# Fi-Pi.net
KiCad netlist of a schematic drawn in EAGLE
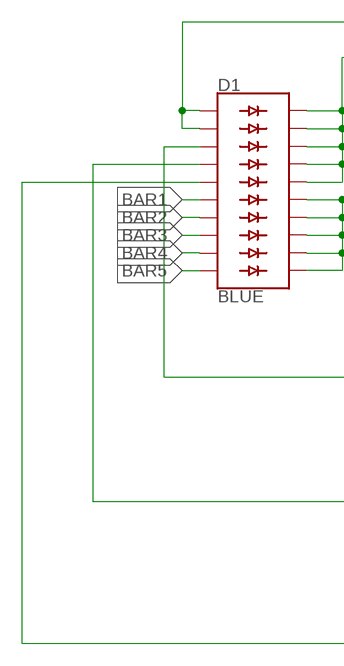
[diagram p0: schematic, sheet 1, part 1 of 2]
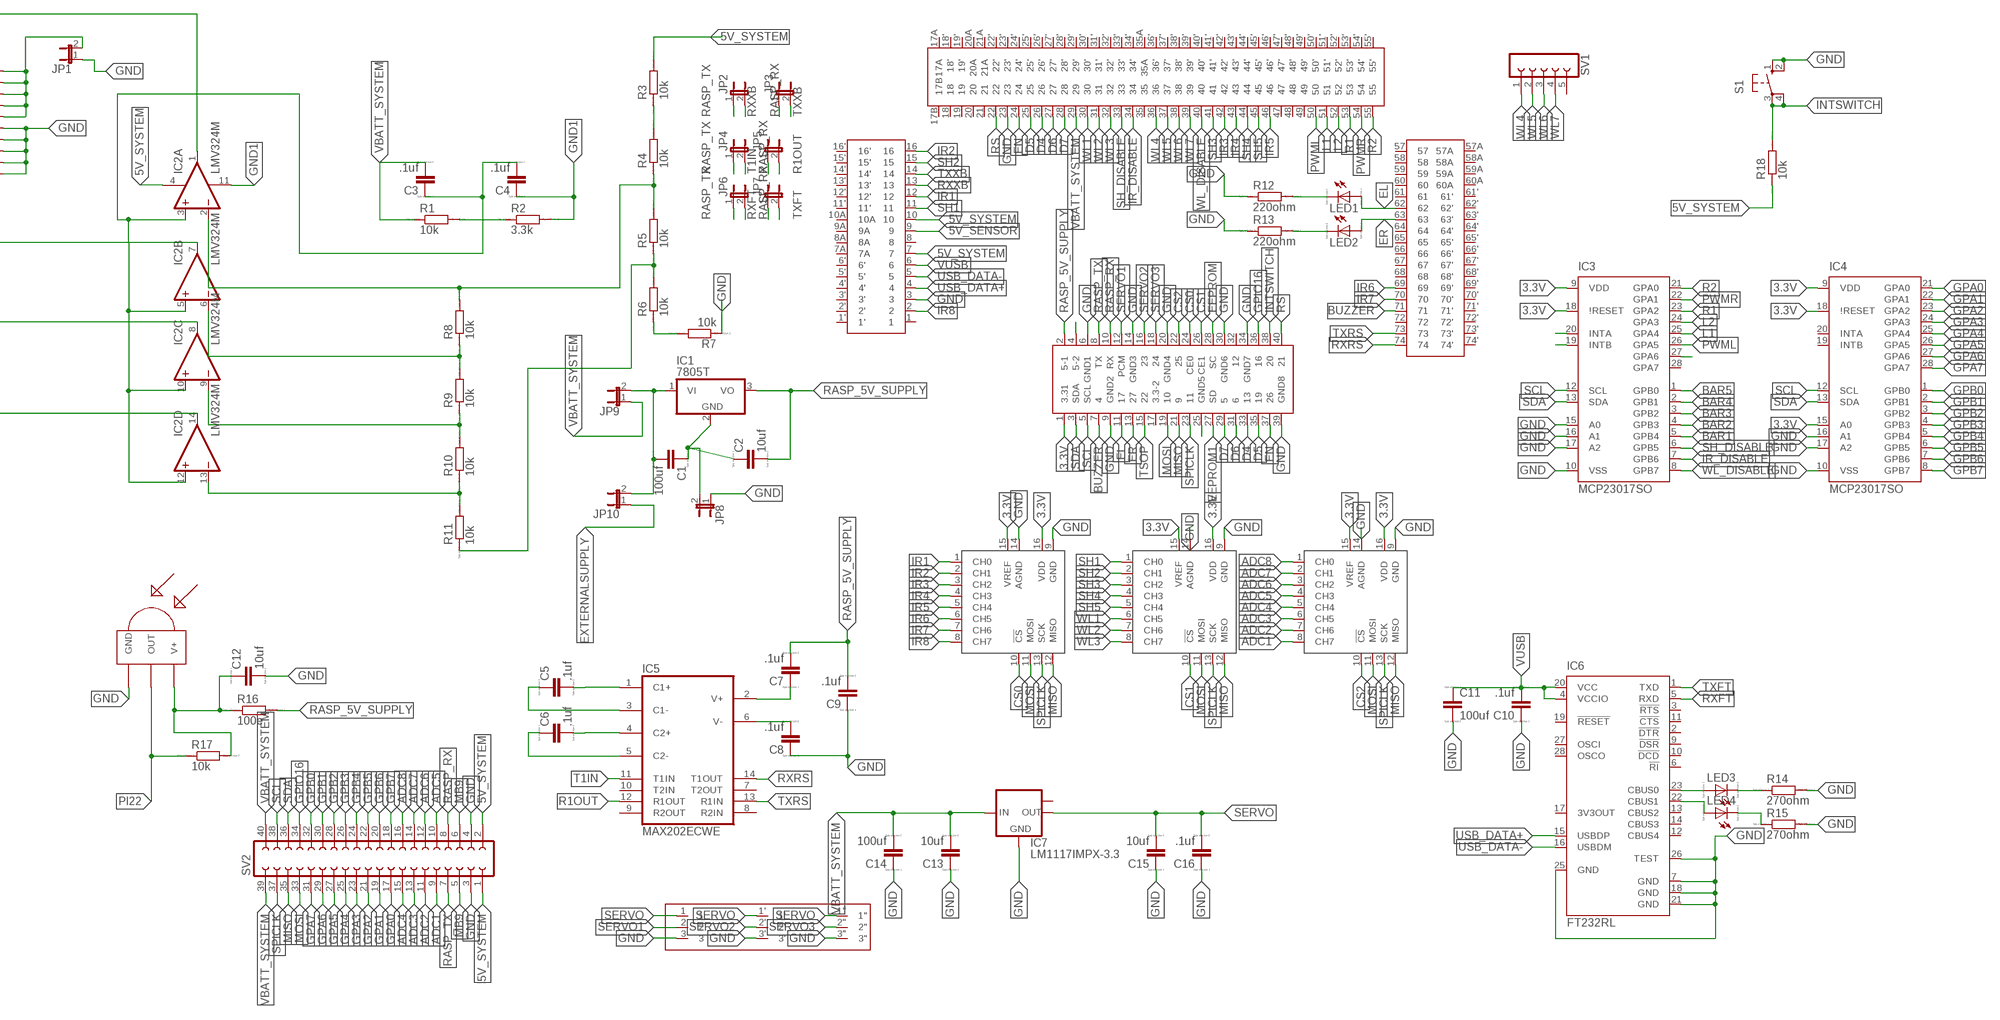
[diagram p1: schematic, sheet 1, part 2 of 2]

(export (version "E")
  (design (tool "Eeschema 10.0.6"))
  (components
    (comp (ref "C1")
      (value "100uf")
      (footprint "eagle-import:C1206")
      (libsource (lib "eagle-import") (part "CC1206"))
    )
    (comp (ref "C2")
      (value "10uf")
      (footprint "eagle-import:C1206")
      (libsource (lib "eagle-import") (part "CC1206"))
    )
    (comp (ref "C3")
      (value ".1uf")
      (footprint "eagle-import:C1206")
      (libsource (lib "eagle-import") (part "CC1206"))
    )
    (comp (ref "C4")
      (value ".1uf")
      (footprint "eagle-import:C1206")
      (libsource (lib "eagle-import") (part "CC1206"))
    )
    (comp (ref "C5")
      (value ".1uf")
      (footprint "eagle-import:C1206")
      (libsource (lib "eagle-import") (part "CC1206"))
    )
    (comp (ref "C6")
      (value ".1uf")
      (footprint "eagle-import:C1206")
      (libsource (lib "eagle-import") (part "CC1206"))
    )
    (comp (ref "C7")
      (value ".1uf")
      (footprint "eagle-import:C1206")
      (libsource (lib "eagle-import") (part "CC1206"))
    )
    (comp (ref "C8")
      (value ".1uf")
      (footprint "eagle-import:C1206")
      (libsource (lib "eagle-import") (part "CC1206"))
    )
    (comp (ref "C9")
      (value ".1uf")
      (footprint "eagle-import:C1206")
      (libsource (lib "eagle-import") (part "CC1206"))
    )
    (comp (ref "C10")
      (value ".1uf")
      (footprint "eagle-import:C1206")
      (libsource (lib "eagle-import") (part "CC1206"))
    )
    (comp (ref "C11")
      (value "100uf")
      (footprint "eagle-import:C1206")
      (libsource (lib "eagle-import") (part "CC1206"))
    )
    (comp (ref "C12")
      (value "10uf")
      (footprint "eagle-import:C1206")
      (libsource (lib "eagle-import") (part "CC1206"))
    )
    (comp (ref "C13")
      (value "10uf")
      (footprint "eagle-import:C1206")
      (libsource (lib "eagle-import") (part "CC1206"))
    )
    (comp (ref "C14")
      (value "100uf")
      (footprint "eagle-import:C1206")
      (libsource (lib "eagle-import") (part "CC1206"))
    )
    (comp (ref "C15")
      (value "10uf")
      (footprint "eagle-import:C1206")
      (libsource (lib "eagle-import") (part "CC1206"))
    )
    (comp (ref "C16")
      (value ".1uf")
      (footprint "eagle-import:C1206")
      (libsource (lib "eagle-import") (part "CC1206"))
    )
    (comp (ref "D1")
      (value "BLUE")
      (footprint "eagle-import:LED_BARGRAPH_10")
      (libsource (lib "eagle-import") (part "LED_BARGRAPH_10BLUE"))
    )
    (comp (ref "IC1")
      (value "7805T")
      (footprint "eagle-import:TO220H")
      (libsource (lib "eagle-import") (part "78T05"))
    )
    (comp (ref "IC2")
      (value "LMV324M")
      (footprint "eagle-import:SO14")
      (libsource (lib "eagle-import") (part "LMV324?M"))
    )
    (comp (ref "IC3")
      (value "MCP23017SO")
      (footprint "eagle-import:SO28W")
      (libsource (lib "eagle-import") (part "MCP23017SO"))
    )
    (comp (ref "IC4")
      (value "MCP23017SO")
      (footprint "eagle-import:SO28W")
      (libsource (lib "eagle-import") (part "MCP23017SO"))
    )
    (comp (ref "IC5")
      (value "MAX202ECWE")
      (footprint "eagle-import:SO16L")
      (fields (field (name "MPN") "MAX202ECWE+T"))
      (libsource (lib "eagle-import") (part "MAX202ECWE"))
    )
    (comp (ref "IC6")
      (value "FT232RL")
      (footprint "eagle-import:SSOP28")
      (libsource (lib "eagle-import") (part "FT232RL"))
    )
    (comp (ref "IC7")
      (value "LM1117IMPX-3.3")
      (footprint "eagle-import:SOT223")
      (libsource (lib "eagle-import") (part "LM1117IMPX-3.3"))
    )
    (comp (ref "JP1")
      (value "JP1E")
      (footprint "eagle-import:JP1")
      (libsource (lib "eagle-import") (part "JP1E"))
    )
    (comp (ref "JP2")
      (value "JP1E")
      (footprint "eagle-import:JP1")
      (libsource (lib "eagle-import") (part "JP1E"))
    )
    (comp (ref "JP3")
      (value "JP1E")
      (footprint "eagle-import:JP1")
      (libsource (lib "eagle-import") (part "JP1E"))
    )
    (comp (ref "JP4")
      (value "JP1E")
      (footprint "eagle-import:JP1")
      (libsource (lib "eagle-import") (part "JP1E"))
    )
    (comp (ref "JP5")
      (value "JP1E")
      (footprint "eagle-import:JP1")
      (libsource (lib "eagle-import") (part "JP1E"))
    )
    (comp (ref "JP6")
      (value "JP1E")
      (footprint "eagle-import:JP1")
      (libsource (lib "eagle-import") (part "JP1E"))
    )
    (comp (ref "JP7")
      (value "JP1E")
      (footprint "eagle-import:JP1")
      (libsource (lib "eagle-import") (part "JP1E"))
    )
    (comp (ref "JP8")
      (value "JP1E")
      (footprint "eagle-import:JP1")
      (libsource (lib "eagle-import") (part "JP1E"))
    )
    (comp (ref "JP9")
      (value "JP1E")
      (footprint "eagle-import:JP1")
      (libsource (lib "eagle-import") (part "JP1E"))
    )
    (comp (ref "JP10")
      (value "JP1E")
      (footprint "eagle-import:JP1")
      (libsource (lib "eagle-import") (part "JP1E"))
    )
    (comp (ref "LED1")
      (value "LED_E")
      (footprint "eagle-import:LED_1206")
      (libsource (lib "eagle-import") (part "LED_E"))
    )
    (comp (ref "LED2")
      (value "LED_E")
      (footprint "eagle-import:LED_1206")
      (libsource (lib "eagle-import") (part "LED_E"))
    )
    (comp (ref "LED3")
      (value "LED_E")
      (footprint "eagle-import:LED_1206")
      (libsource (lib "eagle-import") (part "LED_E"))
    )
    (comp (ref "LED4")
      (value "LED_E")
      (footprint "eagle-import:LED_1206")
      (libsource (lib "eagle-import") (part "LED_E"))
    )
    (comp (ref "R1")
      (value "10k")
      (footprint "eagle-import:R1206")
      (libsource (lib "eagle-import") (part "RR1206"))
    )
    (comp (ref "R2")
      (value "3.3k")
      (footprint "eagle-import:R1206")
      (libsource (lib "eagle-import") (part "RR1206"))
    )
    (comp (ref "R3")
      (value "10k")
      (footprint "eagle-import:R1206")
      (libsource (lib "eagle-import") (part "RR1206"))
    )
    (comp (ref "R4")
      (value "10k")
      (footprint "eagle-import:R1206")
      (libsource (lib "eagle-import") (part "RR1206"))
    )
    (comp (ref "R5")
      (value "10k")
      (footprint "eagle-import:R1206")
      (libsource (lib "eagle-import") (part "RR1206"))
    )
    (comp (ref "R6")
      (value "10k")
      (footprint "eagle-import:R1206")
      (libsource (lib "eagle-import") (part "RR1206"))
    )
    (comp (ref "R7")
      (value "10k")
      (footprint "eagle-import:R1206")
      (libsource (lib "eagle-import") (part "RR1206"))
    )
    (comp (ref "R8")
      (value "10k")
      (footprint "eagle-import:R1206")
      (libsource (lib "eagle-import") (part "RR1206"))
    )
    (comp (ref "R9")
      (value "10k")
      (footprint "eagle-import:R1206")
      (libsource (lib "eagle-import") (part "RR1206"))
    )
    (comp (ref "R10")
      (value "10k")
      (footprint "eagle-import:R1206")
      (libsource (lib "eagle-import") (part "RR1206"))
    )
    (comp (ref "R11")
      (value "10k")
      (footprint "eagle-import:R1206")
      (libsource (lib "eagle-import") (part "RR1206"))
    )
    (comp (ref "R12")
      (value "220ohm")
      (footprint "eagle-import:R1206")
      (libsource (lib "eagle-import") (part "RR1206"))
    )
    (comp (ref "R13")
      (value "220ohm")
      (footprint "eagle-import:R1206")
      (libsource (lib "eagle-import") (part "RR1206"))
    )
    (comp (ref "R14")
      (value "270ohm")
      (footprint "eagle-import:R1206")
      (libsource (lib "eagle-import") (part "RR1206"))
    )
    (comp (ref "R15")
      (value "270ohm")
      (footprint "eagle-import:R1206")
      (libsource (lib "eagle-import") (part "RR1206"))
    )
    (comp (ref "R16")
      (value "100e")
      (footprint "eagle-import:R1206")
      (libsource (lib "eagle-import") (part "RR1206"))
    )
    (comp (ref "R17")
      (value "10k")
      (footprint "eagle-import:R1206")
      (libsource (lib "eagle-import") (part "RR1206"))
    )
    (comp (ref "R18")
      (value "10k")
      (footprint "eagle-import:R1206")
      (libsource (lib "eagle-import") (part "RR1206"))
    )
    (comp (ref "S1")
      (value "10-XX")
      (footprint "eagle-import:B3F-10XX")
      (fields (field (name "MPN") "B3F-1000"))
      (libsource (lib "eagle-import") (part "10-XX"))
    )
    (comp (ref "SV1")
      (value "FE05-1")
      (footprint "eagle-import:FE05-1")
      (libsource (lib "eagle-import") (part "FE05-1"))
    )
    (comp (ref "SV2")
      (value "FE20-2")
      (footprint "eagle-import:FE20-2")
      (libsource (lib "eagle-import") (part "FE20-2"))
    )
    (comp (ref "U$1")
      (value "DAUGHTERBOARDDAUGHTERBOARD")
      (footprint "eagle-import:DAUGHTERBOARD")
      (libsource (lib "eagle-import") (part "DAUGHTERBOARDDAUGHTERBOARD"))
    )
    (comp (ref "U$2")
      (value "MALE_HEADER")
      (footprint "eagle-import:MALE_HEADER_PACKAGE")
      (libsource (lib "eagle-import") (part "MALE_HEADER"))
    )
    (comp (ref "U$3")
      (value "MCP3008SL")
      (footprint "eagle-import:SO16")
      (libsource (lib "eagle-import") (part "MCP3008SL"))
    )
    (comp (ref "U$4")
      (value "MCP3008SL")
      (footprint "eagle-import:SO16")
      (libsource (lib "eagle-import") (part "MCP3008SL"))
    )
    (comp (ref "U$5")
      (value "MCP3008SL")
      (footprint "eagle-import:SO16")
      (libsource (lib "eagle-import") (part "MCP3008SL"))
    )
    (comp (ref "U$6")
      (value "TSOP1738")
      (footprint "eagle-import:TSOP17XX")
      (libsource (lib "eagle-import") (part "TSOP1738"))
    )
    (comp (ref "U$7")
      (value "SERVO")
      (footprint "eagle-import:SERVO")
      (libsource (lib "eagle-import") (part "SERVO"))
    )
  )
  (nets
    (net (code "1") (name "3.3V") (class "Default")
      (node (ref "IC3") (pin "18") (pinfunction "\\~{RESET}_18") (pintype "input"))
      (node (ref "IC3") (pin "9") (pinfunction "VDD_9") (pintype "power_in"))
      (node (ref "IC4") (pin "15") (pinfunction "A0_15") (pintype "input"))
      (node (ref "IC4") (pin "18") (pinfunction "\\~{RESET}_18") (pintype "input"))
      (node (ref "IC4") (pin "9") (pinfunction "VDD_9") (pintype "power_in"))
      (node (ref "U$2") (pin "1") (pinfunction "3.31_1") (pintype "bidirectional"))
      (node (ref "U$3") (pin "15") (pinfunction "VREF_15") (pintype "power_in"))
      (node (ref "U$3") (pin "16") (pinfunction "VDD_16") (pintype "power_in"))
      (node (ref "U$4") (pin "15") (pinfunction "VREF_15") (pintype "power_in"))
      (node (ref "U$4") (pin "16") (pinfunction "VDD_16") (pintype "power_in"))
      (node (ref "U$5") (pin "15") (pinfunction "VREF_15") (pintype "power_in"))
      (node (ref "U$5") (pin "16") (pinfunction "VDD_16") (pintype "power_in"))
    )
    (net (code "2") (name "5V_SENSOR") (class "Default")
      (node (ref "U$1") (pin "9") (pinfunction "9_9") (pintype "output"))
    )
    (net (code "3") (name "5V_SYSTEM") (class "Default")
      (node (ref "IC2") (pin "4") (pinfunction "V+_4") (pintype "power_in"))
      (node (ref "R18") (pin "1") (pinfunction "1_1") (pintype "passive"))
      (node (ref "R3") (pin "2") (pinfunction "2_2") (pintype "passive"))
      (node (ref "SV2") (pin "1") (pinfunction "1_1") (pintype "passive"))
      (node (ref "SV2") (pin "2") (pinfunction "2_2") (pintype "passive"))
      (node (ref "U$1") (pin "10") (pinfunction "10_10") (pintype "output"))
      (node (ref "U$1") (pin "7") (pinfunction "7_7") (pintype "output"))
    )
    (net (code "4") (name "ADC1") (class "Default")
      (node (ref "SV2") (pin "9") (pinfunction "9_9") (pintype "passive"))
      (node (ref "U$5") (pin "8") (pinfunction "CH7_8") (pintype "input"))
    )
    (net (code "5") (name "ADC2") (class "Default")
      (node (ref "SV2") (pin "11") (pinfunction "11_11") (pintype "passive"))
      (node (ref "U$5") (pin "7") (pinfunction "CH6_7") (pintype "input"))
    )
    (net (code "6") (name "ADC3") (class "Default")
      (node (ref "SV2") (pin "13") (pinfunction "13_13") (pintype "passive"))
      (node (ref "U$5") (pin "6") (pinfunction "CH5_6") (pintype "input"))
    )
    (net (code "7") (name "ADC4") (class "Default")
      (node (ref "SV2") (pin "15") (pinfunction "15_15") (pintype "passive"))
      (node (ref "U$5") (pin "5") (pinfunction "CH4_5") (pintype "input"))
    )
    (net (code "8") (name "ADC5") (class "Default")
      (node (ref "SV2") (pin "10") (pinfunction "10_10") (pintype "passive"))
      (node (ref "U$5") (pin "4") (pinfunction "CH3_4") (pintype "input"))
    )
    (net (code "9") (name "ADC6") (class "Default")
      (node (ref "SV2") (pin "12") (pinfunction "12_12") (pintype "passive"))
      (node (ref "U$5") (pin "3") (pinfunction "CH2_3") (pintype "input"))
    )
    (net (code "10") (name "ADC7") (class "Default")
      (node (ref "SV2") (pin "14") (pinfunction "14_14") (pintype "passive"))
      (node (ref "U$5") (pin "2") (pinfunction "CH1_2") (pintype "input"))
    )
    (net (code "11") (name "ADC8") (class "Default")
      (node (ref "SV2") (pin "16") (pinfunction "16_16") (pintype "passive"))
      (node (ref "U$5") (pin "1") (pinfunction "CH0_1") (pintype "input"))
    )
    (net (code "12") (name "BAR1") (class "Default")
      (node (ref "D1") (pin "6") (pinfunction "A5_6") (pintype "passive"))
      (node (ref "IC3") (pin "5") (pinfunction "GPB4_5") (pintype "bidirectional"))
    )
    (net (code "13") (name "BAR2") (class "Default")
      (node (ref "D1") (pin "7") (pinfunction "A6_7") (pintype "passive"))
      (node (ref "IC3") (pin "4") (pinfunction "GPB3_4") (pintype "bidirectional"))
    )
    (net (code "14") (name "BAR3") (class "Default")
      (node (ref "D1") (pin "8") (pinfunction "A7_8") (pintype "passive"))
      (node (ref "IC3") (pin "3") (pinfunction "GPB2_3") (pintype "bidirectional"))
    )
    (net (code "15") (name "BAR4") (class "Default")
      (node (ref "D1") (pin "9") (pinfunction "A8_9") (pintype "passive"))
      (node (ref "IC3") (pin "2") (pinfunction "GPB1_2") (pintype "bidirectional"))
    )
    (net (code "16") (name "BAR5") (class "Default")
      (node (ref "D1") (pin "10") (pinfunction "A9_10") (pintype "passive"))
      (node (ref "IC3") (pin "1") (pinfunction "GPB0_1") (pintype "bidirectional"))
    )
    (net (code "17") (name "BUZZER") (class "Default")
      (node (ref "U$1") (pin "71") (pinfunction "71_71") (pintype "output"))
      (node (ref "U$2") (pin "7") (pinfunction "4_7") (pintype "bidirectional"))
    )
    (net (code "18") (name "CS0") (class "Default")
      (node (ref "U$2") (pin "24") (pinfunction "CE0_24") (pintype "bidirectional"))
      (node (ref "U$3") (pin "10") (pinfunction "~{CS}_10") (pintype "input"))
    )
    (net (code "19") (name "CS1") (class "Default")
      (node (ref "U$2") (pin "26") (pinfunction "CE1_26") (pintype "bidirectional"))
      (node (ref "U$4") (pin "10") (pinfunction "~{CS}_10") (pintype "input"))
    )
    (net (code "20") (name "CS2") (class "Default")
      (node (ref "U$2") (pin "22") (pinfunction "25_22") (pintype "bidirectional"))
      (node (ref "U$5") (pin "10") (pinfunction "~{CS}_10") (pintype "input"))
    )
    (net (code "21") (name "D4") (class "Default")
      (node (ref "U$1") (pin "26") (pinfunction "26_26") (pintype "output"))
      (node (ref "U$2") (pin "33") (pinfunction "13_33") (pintype "bidirectional"))
    )
    (net (code "22") (name "D5") (class "Default")
      (node (ref "U$1") (pin "25") (pinfunction "25_25") (pintype "output"))
      (node (ref "U$2") (pin "35") (pinfunction "19_35") (pintype "bidirectional"))
    )
    (net (code "23") (name "D6") (class "Default")
      (node (ref "U$1") (pin "27") (pinfunction "27_27") (pintype "output"))
      (node (ref "U$2") (pin "31") (pinfunction "6_31") (pintype "bidirectional"))
    )
    (net (code "24") (name "D7") (class "Default")
      (node (ref "U$1") (pin "28") (pinfunction "28_28") (pintype "output"))
      (node (ref "U$2") (pin "29") (pinfunction "5_29") (pintype "bidirectional"))
    )
    (net (code "25") (name "EEPROM") (class "Default")
      (node (ref "U$2") (pin "28") (pinfunction "SC_28") (pintype "bidirectional"))
    )
    (net (code "26") (name "EEPROM1") (class "Default")
      (node (ref "U$2") (pin "27") (pinfunction "SD_27") (pintype "bidirectional"))
    )
    (net (code "27") (name "EL") (class "Default")
      (node (ref "LED1") (pin "A") (pinfunction "A_A") (pintype "passive"))
      (node (ref "U$1") (pin "62") (pinfunction "62_62") (pintype "output"))
      (node (ref "U$2") (pin "11") (pinfunction "17_11") (pintype "bidirectional"))
    )
    (net (code "28") (name "EN") (class "Default")
      (node (ref "U$1") (pin "24") (pinfunction "24_24") (pintype "output"))
      (node (ref "U$2") (pin "37") (pinfunction "26_37") (pintype "bidirectional"))
    )
    (net (code "29") (name "ER") (class "Default")
      (node (ref "LED2") (pin "A") (pinfunction "A_A") (pintype "passive"))
      (node (ref "U$1") (pin "63") (pinfunction "63_63") (pintype "output"))
      (node (ref "U$2") (pin "13") (pinfunction "27_13") (pintype "bidirectional"))
    )
    (net (code "30") (name "EXTERNALSUPPLY") (class "Default")
      (node (ref "JP10") (pin "1") (pinfunction "1_1") (pintype "passive"))
    )
    (net (code "31") (name "GND") (class "Default")
      (node (ref "C10") (pin "1") (pinfunction "1_1") (pintype "passive"))
      (node (ref "C11") (pin "2") (pinfunction "2_2") (pintype "passive"))
      (node (ref "C12") (pin "2") (pinfunction "2_2") (pintype "passive"))
      (node (ref "C13") (pin "1") (pinfunction "1_1") (pintype "passive"))
      (node (ref "C14") (pin "1") (pinfunction "1_1") (pintype "passive"))
      (node (ref "C15") (pin "1") (pinfunction "1_1") (pintype "passive"))
      (node (ref "C16") (pin "1") (pinfunction "1_1") (pintype "passive"))
      (node (ref "C8") (pin "1") (pinfunction "1_1") (pintype "passive"))
      (node (ref "C9") (pin "1") (pinfunction "1_1") (pintype "passive"))
      (node (ref "D1") (pin "11") (pinfunction "C9_11") (pintype "passive"))
      (node (ref "D1") (pin "12") (pinfunction "C8_12") (pintype "passive"))
      (node (ref "D1") (pin "13") (pinfunction "C7_13") (pintype "passive"))
      (node (ref "D1") (pin "14") (pinfunction "C6_14") (pintype "passive"))
      (node (ref "D1") (pin "15") (pinfunction "C5_15") (pintype "passive"))
      (node (ref "IC3") (pin "10") (pinfunction "VSS_10") (pintype "power_in"))
      (node (ref "IC3") (pin "15") (pinfunction "A0_15") (pintype "input"))
      (node (ref "IC3") (pin "16") (pinfunction "A1_16") (pintype "input"))
      (node (ref "IC3") (pin "17") (pinfunction "A2_17") (pintype "input"))
      (node (ref "IC4") (pin "10") (pinfunction "VSS_10") (pintype "power_in"))
      (node (ref "IC4") (pin "16") (pinfunction "A1_16") (pintype "input"))
      (node (ref "IC4") (pin "17") (pinfunction "A2_17") (pintype "input"))
      (node (ref "IC6") (pin "18") (pinfunction "GND_18") (pintype "power_in"))
      (node (ref "IC6") (pin "21") (pinfunction "GND_21") (pintype "power_in"))
      (node (ref "IC6") (pin "25") (pinfunction "GND_25") (pintype "power_in"))
      (node (ref "IC6") (pin "26") (pinfunction "TEST_26") (pintype "input"))
      (node (ref "IC6") (pin "7") (pinfunction "GND_7") (pintype "power_in"))
      (node (ref "IC7") (pin "1") (pinfunction "GND_1") (pintype "input"))
      (node (ref "JP1") (pin "1") (pinfunction "1_1") (pintype "passive"))
      (node (ref "JP8") (pin "1") (pinfunction "1_1") (pintype "passive"))
      (node (ref "R12") (pin "1") (pinfunction "1_1") (pintype "passive"))
      (node (ref "R13") (pin "1") (pinfunction "1_1") (pintype "passive"))
      (node (ref "R14") (pin "2") (pinfunction "2_2") (pintype "passive"))
      (node (ref "R15") (pin "2") (pinfunction "2_2") (pintype "passive"))
      (node (ref "R7") (pin "1") (pinfunction "1_1") (pintype "passive"))
      (node (ref "S1") (pin "1") (pinfunction "S_1") (pintype "passive"))
      (node (ref "S1") (pin "2") (pinfunction "S1_2") (pintype "passive"))
      (node (ref "SV2") (pin "3") (pinfunction "3_3") (pintype "passive"))
      (node (ref "SV2") (pin "4") (pinfunction "4_4") (pintype "passive"))
      (node (ref "U$1") (pin "23") (pinfunction "23_23") (pintype "output"))
      (node (ref "U$1") (pin "3") (pinfunction "3_3") (pintype "output"))
      (node (ref "U$2") (pin "14") (pinfunction "GND3_14") (pintype "bidirectional"))
      (node (ref "U$2") (pin "20") (pinfunction "GND4_20") (pintype "bidirectional"))
      (node (ref "U$2") (pin "25") (pinfunction "GND5_25") (pintype "bidirectional"))
      (node (ref "U$2") (pin "30") (pinfunction "GND6_30") (pintype "bidirectional"))
      (node (ref "U$2") (pin "34") (pinfunction "GND7_34") (pintype "bidirectional"))
      (node (ref "U$2") (pin "39") (pinfunction "GND8_39") (pintype "bidirectional"))
      (node (ref "U$2") (pin "6") (pinfunction "GND1_6") (pintype "bidirectional"))
      (node (ref "U$2") (pin "9") (pinfunction "GND2_9") (pintype "bidirectional"))
      (node (ref "U$3") (pin "14") (pinfunction "AGND_14") (pintype "power_in"))
      (node (ref "U$3") (pin "9") (pinfunction "GND_9") (pintype "power_in"))
      (node (ref "U$4") (pin "14") (pinfunction "AGND_14") (pintype "power_in"))
      (node (ref "U$4") (pin "9") (pinfunction "GND_9") (pintype "power_in"))
      (node (ref "U$5") (pin "14") (pinfunction "AGND_14") (pintype "power_in"))
      (node (ref "U$5") (pin "9") (pinfunction "GND_9") (pintype "power_in"))
      (node (ref "U$6") (pin "GND") (pinfunction "GND_GND") (pintype "bidirectional"))
      (node (ref "U$7") (pin "3") (pinfunction "3_3") (pintype "bidirectional"))
      (node (ref "U$7") (pin "3\"") (pinfunction "3\"_3\"") (pintype "bidirectional"))
      (node (ref "U$7") (pin "3'") (pinfunction "3'_3'") (pintype "bidirectional"))
    )
    (net (code "32") (name "GND1") (class "Default")
      (node (ref "C4") (pin "1") (pinfunction "1_1") (pintype "passive"))
      (node (ref "IC2") (pin "11") (pinfunction "V-_11") (pintype "power_in"))
      (node (ref "R2") (pin "2") (pinfunction "2_2") (pintype "passive"))
    )
    (net (code "33") (name "GPA0") (class "Default")
      (node (ref "IC4") (pin "21") (pinfunction "GPA0_21") (pintype "bidirectional"))
      (node (ref "SV2") (pin "17") (pinfunction "17_17") (pintype "passive"))
    )
    (net (code "34") (name "GPA1") (class "Default")
      (node (ref "IC4") (pin "22") (pinfunction "GPA1_22") (pintype "bidirectional"))
      (node (ref "SV2") (pin "19") (pinfunction "19_19") (pintype "passive"))
    )
    (net (code "35") (name "GPA2") (class "Default")
      (node (ref "IC4") (pin "23") (pinfunction "GPA2_23") (pintype "bidirectional"))
      (node (ref "SV2") (pin "21") (pinfunction "21_21") (pintype "passive"))
    )
    (net (code "36") (name "GPA3") (class "Default")
      (node (ref "IC4") (pin "24") (pinfunction "GPA3_24") (pintype "bidirectional"))
      (node (ref "SV2") (pin "23") (pinfunction "23_23") (pintype "passive"))
    )
    (net (code "37") (name "GPA4") (class "Default")
      (node (ref "IC4") (pin "25") (pinfunction "GPA4_25") (pintype "bidirectional"))
      (node (ref "SV2") (pin "25") (pinfunction "25_25") (pintype "passive"))
    )
    (net (code "38") (name "GPA5") (class "Default")
      (node (ref "IC4") (pin "26") (pinfunction "GPA5_26") (pintype "bidirectional"))
      (node (ref "SV2") (pin "27") (pinfunction "27_27") (pintype "passive"))
    )
    (net (code "39") (name "GPA6") (class "Default")
      (node (ref "IC4") (pin "27") (pinfunction "GPA6_27") (pintype "bidirectional"))
      (node (ref "SV2") (pin "29") (pinfunction "29_29") (pintype "passive"))
    )
    (net (code "40") (name "GPA7") (class "Default")
      (node (ref "IC4") (pin "28") (pinfunction "GPA7_28") (pintype "bidirectional"))
      (node (ref "SV2") (pin "31") (pinfunction "31_31") (pintype "passive"))
    )
    (net (code "41") (name "GPB0") (class "Default")
      (node (ref "IC4") (pin "1") (pinfunction "GPB0_1") (pintype "bidirectional"))
      (node (ref "SV2") (pin "32") (pinfunction "32_32") (pintype "passive"))
    )
    (net (code "42") (name "GPB1") (class "Default")
      (node (ref "IC4") (pin "2") (pinfunction "GPB1_2") (pintype "bidirectional"))
      (node (ref "SV2") (pin "30") (pinfunction "30_30") (pintype "passive"))
    )
    (net (code "43") (name "GPB2") (class "Default")
      (node (ref "IC4") (pin "3") (pinfunction "GPB2_3") (pintype "bidirectional"))
      (node (ref "SV2") (pin "28") (pinfunction "28_28") (pintype "passive"))
    )
    (net (code "44") (name "GPB3") (class "Default")
      (node (ref "IC4") (pin "4") (pinfunction "GPB3_4") (pintype "bidirectional"))
      (node (ref "SV2") (pin "26") (pinfunction "26_26") (pintype "passive"))
    )
    (net (code "45") (name "GPB4") (class "Default")
      (node (ref "IC4") (pin "5") (pinfunction "GPB4_5") (pintype "bidirectional"))
      (node (ref "SV2") (pin "24") (pinfunction "24_24") (pintype "passive"))
    )
    (net (code "46") (name "GPB5") (class "Default")
      (node (ref "IC4") (pin "6") (pinfunction "GPB5_6") (pintype "bidirectional"))
      (node (ref "SV2") (pin "22") (pinfunction "22_22") (pintype "passive"))
    )
    (net (code "47") (name "GPB6") (class "Default")
      (node (ref "IC4") (pin "7") (pinfunction "GPB6_7") (pintype "bidirectional"))
      (node (ref "SV2") (pin "20") (pinfunction "20_20") (pintype "passive"))
    )
    (net (code "48") (name "GPB7") (class "Default")
      (node (ref "IC4") (pin "8") (pinfunction "GPB7_8") (pintype "bidirectional"))
      (node (ref "SV2") (pin "18") (pinfunction "18_18") (pintype "passive"))
    )
    (net (code "49") (name "GPIO16") (class "Default")
      (node (ref "SV2") (pin "34") (pinfunction "34_34") (pintype "passive"))
      (node (ref "U$2") (pin "36") (pinfunction "16_36") (pintype "bidirectional"))
    )
    (net (code "50") (name "INTSWITCH") (class "Default")
      (node (ref "R18") (pin "2") (pinfunction "2_2") (pintype "passive"))
      (node (ref "S1") (pin "3") (pinfunction "P_3") (pintype "passive"))
      (node (ref "S1") (pin "4") (pinfunction "P1_4") (pintype "passive"))
      (node (ref "U$2") (pin "38") (pinfunction "20_38") (pintype "bidirectional"))
    )
    (net (code "51") (name "IR1") (class "Default")
      (node (ref "U$1") (pin "12") (pinfunction "12_12") (pintype "output"))
      (node (ref "U$3") (pin "1") (pinfunction "CH0_1") (pintype "input"))
    )
    (net (code "52") (name "IR2") (class "Default")
      (node (ref "U$1") (pin "16") (pinfunction "16_16") (pintype "output"))
      (node (ref "U$3") (pin "2") (pinfunction "CH1_2") (pintype "input"))
    )
    (net (code "53") (name "IR3") (class "Default")
      (node (ref "U$1") (pin "42") (pinfunction "42_42") (pintype "output"))
      (node (ref "U$3") (pin "3") (pinfunction "CH2_3") (pintype "input"))
    )
    (net (code "54") (name "IR4") (class "Default")
      (node (ref "U$1") (pin "43") (pinfunction "43_43") (pintype "output"))
      (node (ref "U$3") (pin "4") (pinfunction "CH3_4") (pintype "input"))
    )
    (net (code "55") (name "IR5") (class "Default")
      (node (ref "U$1") (pin "46") (pinfunction "46_46") (pintype "output"))
      (node (ref "U$3") (pin "5") (pinfunction "CH4_5") (pintype "input"))
    )
    (net (code "56") (name "IR6") (class "Default")
      (node (ref "U$1") (pin "69") (pinfunction "69_69") (pintype "output"))
      (node (ref "U$3") (pin "6") (pinfunction "CH5_6") (pintype "input"))
    )
    (net (code "57") (name "IR7") (class "Default")
      (node (ref "U$1") (pin "70") (pinfunction "70_70") (pintype "output"))
      (node (ref "U$3") (pin "7") (pinfunction "CH6_7") (pintype "input"))
    )
    (net (code "58") (name "IR8") (class "Default")
      (node (ref "U$1") (pin "2") (pinfunction "2_2") (pintype "output"))
      (node (ref "U$3") (pin "8") (pinfunction "CH7_8") (pintype "input"))
    )
    (net (code "59") (name "IR_DISABLE") (class "Default")
      (node (ref "IC3") (pin "7") (pinfunction "GPB6_7") (pintype "bidirectional"))
      (node (ref "U$1") (pin "34") (pinfunction "34_34") (pintype "output"))
    )
    (net (code "60") (name "L1") (class "Default")
      (node (ref "IC3") (pin "25") (pinfunction "GPA4_25") (pintype "bidirectional"))
      (node (ref "U$1") (pin "51") (pinfunction "51_51") (pintype "output"))
    )
    (net (code "61") (name "L2") (class "Default")
      (node (ref "IC3") (pin "24") (pinfunction "GPA3_24") (pintype "bidirectional"))
      (node (ref "U$1") (pin "52") (pinfunction "52_52") (pintype "output"))
    )
    (net (code "62") (name "MB9") (class "Default")
      (node (ref "SV2") (pin "5") (pinfunction "5_5") (pintype "passive"))
      (node (ref "SV2") (pin "6") (pinfunction "6_6") (pintype "passive"))
    )
    (net (code "63") (name "MISO") (class "Default")
      (node (ref "SV2") (pin "35") (pinfunction "35_35") (pintype "passive"))
      (node (ref "U$2") (pin "21") (pinfunction "9_21") (pintype "bidirectional"))
      (node (ref "U$3") (pin "12") (pinfunction "MISO_12") (pintype "output"))
      (node (ref "U$4") (pin "12") (pinfunction "MISO_12") (pintype "output"))
      (node (ref "U$5") (pin "12") (pinfunction "MISO_12") (pintype "output"))
    )
    (net (code "64") (name "MOSI") (class "Default")
      (node (ref "SV2") (pin "33") (pinfunction "33_33") (pintype "passive"))
      (node (ref "U$2") (pin "19") (pinfunction "10_19") (pintype "bidirectional"))
      (node (ref "U$3") (pin "11") (pinfunction "MOSI_11") (pintype "input"))
      (node (ref "U$4") (pin "11") (pinfunction "MOSI_11") (pintype "input"))
      (node (ref "U$5") (pin "11") (pinfunction "MOSI_11") (pintype "input"))
    )
    (net (code "65") (name "Net-(C12-Pad1)") (class "Default")
      (node (ref "C12") (pin "1") (pinfunction "1_1") (pintype "passive"))
      (node (ref "R16") (pin "1") (pinfunction "1_1") (pintype "passive"))
      (node (ref "R17") (pin "2") (pinfunction "2_2") (pintype "passive"))
      (node (ref "U$6") (pin "V+") (pinfunction "V+_V+") (pintype "bidirectional"))
    )
    (net (code "66") (name "Net-(D1-A)") (class "Default")
      (node (ref "D1") (pin "1") (pinfunction "A_1") (pintype "passive"))
      (node (ref "D1") (pin "2") (pinfunction "A1_2") (pintype "passive"))
      (node (ref "IC2") (pin "1") (pinfunction "OUT_1") (pintype "output"))
    )
    (net (code "67") (name "Net-(D1-A2)") (class "Default")
      (node (ref "D1") (pin "3") (pinfunction "A2_3") (pintype "passive"))
      (node (ref "IC2") (pin "7") (pinfunction "OUT_7") (pintype "output"))
    )
    (net (code "68") (name "Net-(D1-A3)") (class "Default")
      (node (ref "D1") (pin "4") (pinfunction "A3_4") (pintype "passive"))
      (node (ref "IC2") (pin "8") (pinfunction "OUT_8") (pintype "output"))
    )
    (net (code "69") (name "Net-(D1-A4)") (class "Default")
      (node (ref "D1") (pin "5") (pinfunction "A4_5") (pintype "passive"))
      (node (ref "IC2") (pin "14") (pinfunction "OUT_14") (pintype "output"))
    )
    (net (code "70") (name "Net-(D1-C)") (class "Default")
      (node (ref "D1") (pin "16") (pinfunction "C4_16") (pintype "passive"))
      (node (ref "D1") (pin "17") (pinfunction "C3_17") (pintype "passive"))
      (node (ref "D1") (pin "18") (pinfunction "C2_18") (pintype "passive"))
      (node (ref "D1") (pin "19") (pinfunction "C1_19") (pintype "passive"))
      (node (ref "D1") (pin "20") (pinfunction "C_20") (pintype "passive"))
      (node (ref "JP1") (pin "2") (pinfunction "2_2") (pintype "passive"))
    )
    (net (code "71") (name "Net-(IC1-GND)") (class "Default")
      (node (ref "C1") (pin "1") (pinfunction "1_1") (pintype "passive"))
      (node (ref "C2") (pin "1") (pinfunction "1_1") (pintype "passive"))
      (node (ref "IC1") (pin "2") (pinfunction "GND_2") (pintype "passive"))
      (node (ref "JP8") (pin "2") (pinfunction "2_2") (pintype "passive"))
    )
    (net (code "72") (name "Net-(IC2A-+IN)") (class "Default")
      (node (ref "C3") (pin "1") (pinfunction "1_1") (pintype "passive"))
      (node (ref "C4") (pin "2") (pinfunction "2_2") (pintype "passive"))
      (node (ref "IC2") (pin "10") (pinfunction "+IN_10") (pintype "input"))
      (node (ref "IC2") (pin "12") (pinfunction "+IN_12") (pintype "input"))
      (node (ref "IC2") (pin "3") (pinfunction "+IN_3") (pintype "input"))
      (node (ref "IC2") (pin "5") (pinfunction "+IN_5") (pintype "input"))
      (node (ref "R1") (pin "2") (pinfunction "2_2") (pintype "passive"))
      (node (ref "R2") (pin "1") (pinfunction "1_1") (pintype "passive"))
    )
    (net (code "73") (name "Net-(IC2A--IN)") (class "Default")
      (node (ref "IC2") (pin "2") (pinfunction "-IN_2") (pintype "input"))
      (node (ref "R4") (pin "1") (pinfunction "1_1") (pintype "passive"))
      (node (ref "R5") (pin "2") (pinfunction "2_2") (pintype "passive"))
      (node (ref "R8") (pin "2") (pinfunction "2_2") (pintype "passive"))
    )
    (net (code "74") (name "Net-(IC2B--IN)") (class "Default")
      (node (ref "IC2") (pin "6") (pinfunction "-IN_6") (pintype "input"))
      (node (ref "R8") (pin "1") (pinfunction "1_1") (pintype "passive"))
      (node (ref "R9") (pin "2") (pinfunction "2_2") (pintype "passive"))
    )
    (net (code "75") (name "Net-(IC2C--IN)") (class "Default")
      (node (ref "IC2") (pin "9") (pinfunction "-IN_9") (pintype "input"))
      (node (ref "R10") (pin "2") (pinfunction "2_2") (pintype "passive"))
      (node (ref "R9") (pin "1") (pinfunction "1_1") (pintype "passive"))
    )
    (net (code "76") (name "Net-(IC2D--IN)") (class "Default")
      (node (ref "IC2") (pin "13") (pinfunction "-IN_13") (pintype "input"))
      (node (ref "R10") (pin "1") (pinfunction "1_1") (pintype "passive"))
      (node (ref "R11") (pin "2") (pinfunction "2_2") (pintype "passive"))
    )
    (net (code "77") (name "Net-(IC5A-C1+)") (class "Default")
      (node (ref "C5") (pin "2") (pinfunction "2_2") (pintype "passive"))
      (node (ref "IC5") (pin "1") (pinfunction "C1+_1") (pintype "bidirectional"))
    )
    (net (code "78") (name "Net-(IC5A-C1-)") (class "Default")
      (node (ref "C5") (pin "1") (pinfunction "1_1") (pintype "passive"))
      (node (ref "IC5") (pin "3") (pinfunction "C1-_3") (pintype "bidirectional"))
    )
    (net (code "79") (name "Net-(IC5A-C2+)") (class "Default")
      (node (ref "C6") (pin "2") (pinfunction "2_2") (pintype "passive"))
      (node (ref "IC5") (pin "4") (pinfunction "C2+_4") (pintype "bidirectional"))
    )
    (net (code "80") (name "Net-(IC5A-C2-)") (class "Default")
      (node (ref "C6") (pin "1") (pinfunction "1_1") (pintype "passive"))
      (node (ref "IC5") (pin "5") (pinfunction "C2-_5") (pintype "bidirectional"))
    )
    (net (code "81") (name "Net-(IC5A-V+)") (class "Default")
      (node (ref "C7") (pin "1") (pinfunction "1_1") (pintype "passive"))
      (node (ref "IC5") (pin "2") (pinfunction "V+_2") (pintype "bidirectional"))
    )
    (net (code "82") (name "Net-(IC5A-V-)") (class "Default")
      (node (ref "C8") (pin "2") (pinfunction "2_2") (pintype "passive"))
      (node (ref "IC5") (pin "6") (pinfunction "V-_6") (pintype "bidirectional"))
    )
    (net (code "83") (name "Net-(IC6-CBUS0)") (class "Default")
      (node (ref "IC6") (pin "23") (pinfunction "CBUS0_23") (pintype "bidirectional"))
      (node (ref "LED3") (pin "A") (pinfunction "A_A") (pintype "passive"))
    )
    (net (code "84") (name "Net-(IC6-CBUS1)") (class "Default")
      (node (ref "IC6") (pin "22") (pinfunction "CBUS1_22") (pintype "bidirectional"))
      (node (ref "LED4") (pin "A") (pinfunction "A_A") (pintype "passive"))
    )
    (net (code "85") (name "Net-(LED1-PadC)") (class "Default")
      (node (ref "LED1") (pin "C") (pinfunction "C_C") (pintype "passive"))
      (node (ref "R12") (pin "2") (pinfunction "2_2") (pintype "passive"))
    )
    (net (code "86") (name "Net-(LED2-PadC)") (class "Default")
      (node (ref "LED2") (pin "C") (pinfunction "C_C") (pintype "passive"))
      (node (ref "R13") (pin "2") (pinfunction "2_2") (pintype "passive"))
    )
    (net (code "87") (name "Net-(LED3-PadC)") (class "Default")
      (node (ref "LED3") (pin "C") (pinfunction "C_C") (pintype "passive"))
      (node (ref "R14") (pin "1") (pinfunction "1_1") (pintype "passive"))
    )
    (net (code "88") (name "Net-(LED4-PadC)") (class "Default")
      (node (ref "LED4") (pin "C") (pinfunction "C_C") (pintype "passive"))
      (node (ref "R15") (pin "1") (pinfunction "1_1") (pintype "passive"))
    )
    (net (code "89") (name "Net-(R3-Pad1)") (class "Default")
      (node (ref "R3") (pin "1") (pinfunction "1_1") (pintype "passive"))
      (node (ref "R4") (pin "2") (pinfunction "2_2") (pintype "passive"))
    )
    (net (code "90") (name "Net-(R6-Pad1)") (class "Default")
      (node (ref "R6") (pin "1") (pinfunction "1_1") (pintype "passive"))
      (node (ref "R7") (pin "2") (pinfunction "2_2") (pintype "passive"))
    )
    (net (code "91") (name "Net-(R11-Pad1)") (class "Default")
      (node (ref "R11") (pin "1") (pinfunction "1_1") (pintype "passive"))
      (node (ref "R5") (pin "1") (pinfunction "1_1") (pintype "passive"))
      (node (ref "R6") (pin "2") (pinfunction "2_2") (pintype "passive"))
    )
    (net (code "92") (name "PI22") (class "Default")
      (node (ref "R17") (pin "1") (pinfunction "1_1") (pintype "passive"))
      (node (ref "U$6") (pin "OUT") (pinfunction "OUT_OUT") (pintype "bidirectional"))
    )
    (net (code "93") (name "PWML") (class "Default")
      (node (ref "IC3") (pin "26") (pinfunction "GPA5_26") (pintype "bidirectional"))
      (node (ref "U$1") (pin "50") (pinfunction "50_50") (pintype "output"))
    )
    (net (code "94") (name "PWMR") (class "Default")
      (node (ref "IC3") (pin "22") (pinfunction "GPA1_22") (pintype "bidirectional"))
      (node (ref "U$1") (pin "54") (pinfunction "54_54") (pintype "output"))
    )
    (net (code "95") (name "R1") (class "Default")
      (node (ref "IC3") (pin "23") (pinfunction "GPA2_23") (pintype "bidirectional"))
      (node (ref "U$1") (pin "53") (pinfunction "53_53") (pintype "output"))
    )
    (net (code "96") (name "R1OUT") (class "Default")
      (node (ref "IC5") (pin "12") (pinfunction "R1OUT_12") (pintype "output"))
      (node (ref "JP5") (pin "2") (pinfunction "2_2") (pintype "passive"))
    )
    (net (code "97") (name "R2") (class "Default")
      (node (ref "IC3") (pin "21") (pinfunction "GPA0_21") (pintype "bidirectional"))
      (node (ref "U$1") (pin "55") (pinfunction "55_55") (pintype "output"))
    )
    (net (code "98") (name "RASP_5V_SUPPLY") (class "Default")
      (node (ref "C2") (pin "2") (pinfunction "2_2") (pintype "passive"))
      (node (ref "C7") (pin "2") (pinfunction "2_2") (pintype "passive"))
      (node (ref "C9") (pin "2") (pinfunction "2_2") (pintype "passive"))
      (node (ref "IC1") (pin "3") (pinfunction "VO_3") (pintype "passive"))
      (node (ref "R16") (pin "2") (pinfunction "2_2") (pintype "passive"))
      (node (ref "U$2") (pin "2") (pinfunction "5-1_2") (pintype "bidirectional"))
    )
    (net (code "99") (name "RASP_RX") (class "Default")
      (node (ref "JP3") (pin "1") (pinfunction "1_1") (pintype "passive"))
      (node (ref "JP5") (pin "1") (pinfunction "1_1") (pintype "passive"))
      (node (ref "JP7") (pin "1") (pinfunction "1_1") (pintype "passive"))
      (node (ref "SV2") (pin "8") (pinfunction "8_8") (pintype "passive"))
      (node (ref "U$2") (pin "10") (pinfunction "RX_10") (pintype "bidirectional"))
    )
    (net (code "100") (name "RASP_TX") (class "Default")
      (node (ref "JP2") (pin "1") (pinfunction "1_1") (pintype "passive"))
      (node (ref "JP4") (pin "1") (pinfunction "1_1") (pintype "passive"))
      (node (ref "JP6") (pin "1") (pinfunction "1_1") (pintype "passive"))
      (node (ref "SV2") (pin "7") (pinfunction "7_7") (pintype "passive"))
      (node (ref "U$2") (pin "8") (pinfunction "TX_8") (pintype "bidirectional"))
    )
    (net (code "101") (name "RS") (class "Default")
      (node (ref "U$1") (pin "22") (pinfunction "22_22") (pintype "output"))
      (node (ref "U$2") (pin "40") (pinfunction "21_40") (pintype "bidirectional"))
    )
    (net (code "102") (name "RXFT") (class "Default")
      (node (ref "IC6") (pin "5") (pinfunction "RXD_5") (pintype "input"))
      (node (ref "JP6") (pin "2") (pinfunction "2_2") (pintype "passive"))
    )
    (net (code "103") (name "RXRS") (class "Default")
      (node (ref "IC5") (pin "14") (pinfunction "T1OUT_14") (pintype "output"))
      (node (ref "U$1") (pin "74") (pinfunction "74_74") (pintype "output"))
    )
    (net (code "104") (name "RXXB") (class "Default")
      (node (ref "JP2") (pin "2") (pinfunction "2_2") (pintype "passive"))
      (node (ref "U$1") (pin "13") (pinfunction "13_13") (pintype "output"))
    )
    (net (code "105") (name "SCL") (class "Default")
      (node (ref "IC3") (pin "12") (pinfunction "SCL_12") (pintype "input"))
      (node (ref "IC4") (pin "12") (pinfunction "SCL_12") (pintype "input"))
      (node (ref "SV2") (pin "38") (pinfunction "38_38") (pintype "passive"))
      (node (ref "U$2") (pin "5") (pinfunction "SCL_5") (pintype "bidirectional"))
    )
    (net (code "106") (name "SDA") (class "Default")
      (node (ref "IC3") (pin "13") (pinfunction "SDA_13") (pintype "bidirectional"))
      (node (ref "IC4") (pin "13") (pinfunction "SDA_13") (pintype "bidirectional"))
      (node (ref "SV2") (pin "36") (pinfunction "36_36") (pintype "passive"))
      (node (ref "U$2") (pin "3") (pinfunction "SDA_3") (pintype "bidirectional"))
    )
    (net (code "107") (name "SERVO") (class "Default")
      (node (ref "C15") (pin "2") (pinfunction "2_2") (pintype "passive"))
      (node (ref "C16") (pin "2") (pinfunction "2_2") (pintype "passive"))
      (node (ref "IC7") (pin "2") (pinfunction "OUT_2") (pintype "passive"))
      (node (ref "U$7") (pin "1") (pinfunction "1_1") (pintype "bidirectional"))
      (node (ref "U$7") (pin "1\"") (pinfunction "1\"_1\"") (pintype "bidirectional"))
      (node (ref "U$7") (pin "1'") (pinfunction "1'_1'") (pintype "bidirectional"))
    )
    (net (code "108") (name "SERVO1") (class "Default")
      (node (ref "U$2") (pin "12") (pinfunction "PCM_12") (pintype "bidirectional"))
      (node (ref "U$7") (pin "2") (pinfunction "2_2") (pintype "bidirectional"))
    )
    (net (code "109") (name "SERVO2") (class "Default")
      (node (ref "U$2") (pin "16") (pinfunction "23_16") (pintype "bidirectional"))
      (node (ref "U$7") (pin "2'") (pinfunction "2'_2'") (pintype "bidirectional"))
    )
    (net (code "110") (name "SERVO3") (class "Default")
      (node (ref "U$2") (pin "18") (pinfunction "24_18") (pintype "bidirectional"))
      (node (ref "U$7") (pin "2\"") (pinfunction "2\"_2\"") (pintype "bidirectional"))
    )
    (net (code "111") (name "SH1") (class "Default")
      (node (ref "U$1") (pin "11") (pinfunction "11_11") (pintype "output"))
      (node (ref "U$4") (pin "1") (pinfunction "CH0_1") (pintype "input"))
    )
    (net (code "112") (name "SH2") (class "Default")
      (node (ref "U$1") (pin "15") (pinfunction "15_15") (pintype "output"))
      (node (ref "U$4") (pin "2") (pinfunction "CH1_2") (pintype "input"))
    )
    (net (code "113") (name "SH3") (class "Default")
      (node (ref "U$1") (pin "41") (pinfunction "41_41") (pintype "output"))
      (node (ref "U$4") (pin "3") (pinfunction "CH2_3") (pintype "input"))
    )
    (net (code "114") (name "SH4") (class "Default")
      (node (ref "U$1") (pin "44") (pinfunction "44_44") (pintype "output"))
      (node (ref "U$4") (pin "4") (pinfunction "CH3_4") (pintype "input"))
    )
    (net (code "115") (name "SH5") (class "Default")
      (node (ref "U$1") (pin "45") (pinfunction "45_45") (pintype "output"))
      (node (ref "U$4") (pin "5") (pinfunction "CH4_5") (pintype "input"))
    )
    (net (code "116") (name "SH_DISABLE") (class "Default")
      (node (ref "IC3") (pin "6") (pinfunction "GPB5_6") (pintype "bidirectional"))
      (node (ref "U$1") (pin "33") (pinfunction "33_33") (pintype "output"))
    )
    (net (code "117") (name "SPICLK") (class "Default")
      (node (ref "SV2") (pin "37") (pinfunction "37_37") (pintype "passive"))
      (node (ref "U$2") (pin "23") (pinfunction "11_23") (pintype "bidirectional"))
      (node (ref "U$3") (pin "13") (pinfunction "SCK_13") (pintype "input"))
      (node (ref "U$4") (pin "13") (pinfunction "SCK_13") (pintype "input"))
      (node (ref "U$5") (pin "13") (pinfunction "SCK_13") (pintype "input"))
    )
    (net (code "118") (name "T1IN") (class "Default")
      (node (ref "IC5") (pin "11") (pinfunction "T1IN_11") (pintype "input"))
      (node (ref "JP4") (pin "2") (pinfunction "2_2") (pintype "passive"))
    )
    (net (code "119") (name "TSOP") (class "Default")
      (node (ref "U$2") (pin "15") (pinfunction "22_15") (pintype "bidirectional"))
    )
    (net (code "120") (name "TXFT") (class "Default")
      (node (ref "IC6") (pin "1") (pinfunction "TXD_1") (pintype "output"))
      (node (ref "JP7") (pin "2") (pinfunction "2_2") (pintype "passive"))
    )
    (net (code "121") (name "TXRS") (class "Default")
      (node (ref "IC5") (pin "13") (pinfunction "R1IN_13") (pintype "input"))
      (node (ref "U$1") (pin "73") (pinfunction "73_73") (pintype "output"))
    )
    (net (code "122") (name "TXXB") (class "Default")
      (node (ref "JP3") (pin "2") (pinfunction "2_2") (pintype "passive"))
      (node (ref "U$1") (pin "14") (pinfunction "14_14") (pintype "output"))
    )
    (net (code "123") (name "USB_DATA+") (class "Default")
      (node (ref "IC6") (pin "15") (pinfunction "USBDP_15") (pintype "bidirectional"))
      (node (ref "U$1") (pin "4") (pinfunction "4_4") (pintype "output"))
    )
    (net (code "124") (name "USB_DATA-") (class "Default")
      (node (ref "IC6") (pin "16") (pinfunction "USBDM_16") (pintype "bidirectional"))
      (node (ref "U$1") (pin "5") (pinfunction "5_5") (pintype "output"))
    )
    (net (code "125") (name "VBATT_SYSTEM") (class "Default")
      (node (ref "C1") (pin "2") (pinfunction "2_2") (pintype "passive"))
      (node (ref "C13") (pin "2") (pinfunction "2_2") (pintype "passive"))
      (node (ref "C14") (pin "2") (pinfunction "2_2") (pintype "passive"))
      (node (ref "C3") (pin "2") (pinfunction "2_2") (pintype "passive"))
      (node (ref "IC1") (pin "1") (pinfunction "VI_1") (pintype "input"))
      (node (ref "IC7") (pin "3") (pinfunction "IN_3") (pintype "input"))
      (node (ref "JP10") (pin "2") (pinfunction "2_2") (pintype "passive"))
      (node (ref "JP9") (pin "1") (pinfunction "1_1") (pintype "passive"))
      (node (ref "JP9") (pin "2") (pinfunction "2_2") (pintype "passive"))
      (node (ref "R1") (pin "1") (pinfunction "1_1") (pintype "passive"))
      (node (ref "SV2") (pin "39") (pinfunction "39_39") (pintype "passive"))
      (node (ref "SV2") (pin "40") (pinfunction "40_40") (pintype "passive"))
      (node (ref "U$1") (pin "29") (pinfunction "29_29") (pintype "output"))
    )
    (net (code "126") (name "VUSB") (class "Default")
      (node (ref "C10") (pin "2") (pinfunction "2_2") (pintype "passive"))
      (node (ref "C11") (pin "1") (pinfunction "1_1") (pintype "passive"))
      (node (ref "IC6") (pin "20") (pinfunction "VCC_20") (pintype "power_in"))
      (node (ref "IC6") (pin "4") (pinfunction "VCCIO_4") (pintype "power_in"))
      (node (ref "U$1") (pin "6") (pinfunction "6_6") (pintype "output"))
    )
    (net (code "127") (name "WL1") (class "Default")
      (node (ref "U$1") (pin "30") (pinfunction "30_30") (pintype "output"))
      (node (ref "U$4") (pin "6") (pinfunction "CH5_6") (pintype "input"))
    )
    (net (code "128") (name "WL2") (class "Default")
      (node (ref "U$1") (pin "31") (pinfunction "31_31") (pintype "output"))
      (node (ref "U$4") (pin "7") (pinfunction "CH6_7") (pintype "input"))
    )
    (net (code "129") (name "WL3") (class "Default")
      (node (ref "U$1") (pin "32") (pinfunction "32_32") (pintype "output"))
      (node (ref "U$4") (pin "8") (pinfunction "CH7_8") (pintype "input"))
    )
    (net (code "130") (name "WL4") (class "Default")
      (node (ref "SV1") (pin "1") (pinfunction "1_1") (pintype "passive"))
      (node (ref "U$1") (pin "36") (pinfunction "36_36") (pintype "output"))
    )
    (net (code "131") (name "WL5") (class "Default")
      (node (ref "SV1") (pin "2") (pinfunction "2_2") (pintype "passive"))
      (node (ref "U$1") (pin "37") (pinfunction "37_37") (pintype "output"))
    )
    (net (code "132") (name "WL6") (class "Default")
      (node (ref "SV1") (pin "3") (pinfunction "3_3") (pintype "passive"))
      (node (ref "U$1") (pin "38") (pinfunction "38_38") (pintype "output"))
    )
    (net (code "133") (name "WL7") (class "Default")
      (node (ref "SV1") (pin "4") (pinfunction "4_4") (pintype "passive"))
      (node (ref "U$1") (pin "39") (pinfunction "39_39") (pintype "output"))
    )
    (net (code "134") (name "WL_DISABLE") (class "Default")
      (node (ref "IC3") (pin "8") (pinfunction "GPB7_8") (pintype "bidirectional"))
      (node (ref "U$1") (pin "40") (pinfunction "40_40") (pintype "output"))
    )
    (net (code "135") (name "unconnected-(IC3-GPA6-Pad27)") (class "Default")
      (node (ref "IC3") (pin "27") (pinfunction "GPA6_27") (pintype "bidirectional"))
    )
    (net (code "136") (name "unconnected-(IC3-GPA7-Pad28)") (class "Default")
      (node (ref "IC3") (pin "28") (pinfunction "GPA7_28") (pintype "bidirectional"))
    )
    (net (code "137") (name "unconnected-(IC3-INTA-Pad20)") (class "Default")
      (node (ref "IC3") (pin "20") (pinfunction "INTA_20") (pintype "output"))
    )
    (net (code "138") (name "unconnected-(IC3-INTB-Pad19)") (class "Default")
      (node (ref "IC3") (pin "19") (pinfunction "INTB_19") (pintype "output"))
    )
    (net (code "139") (name "unconnected-(IC4-INTA-Pad20)") (class "Default")
      (node (ref "IC4") (pin "20") (pinfunction "INTA_20") (pintype "output"))
    )
    (net (code "140") (name "unconnected-(IC4-INTB-Pad19)") (class "Default")
      (node (ref "IC4") (pin "19") (pinfunction "INTB_19") (pintype "output"))
    )
    (net (code "141") (name "unconnected-(IC5A-R2IN-Pad8)") (class "Default")
      (node (ref "IC5") (pin "8") (pinfunction "R2IN_8") (pintype "input"))
    )
    (net (code "142") (name "unconnected-(IC5A-R2OUT-Pad9)") (class "Default")
      (node (ref "IC5") (pin "9") (pinfunction "R2OUT_9") (pintype "output"))
    )
    (net (code "143") (name "unconnected-(IC5A-T2IN-Pad10)") (class "Default")
      (node (ref "IC5") (pin "10") (pinfunction "T2IN_10") (pintype "input"))
    )
    (net (code "144") (name "unconnected-(IC5A-T2OUT-Pad7)") (class "Default")
      (node (ref "IC5") (pin "7") (pinfunction "T2OUT_7") (pintype "output"))
    )
    (net (code "145") (name "unconnected-(IC6-3V3OUT-Pad17)") (class "Default")
      (node (ref "IC6") (pin "17") (pinfunction "3V3OUT_17") (pintype "output"))
    )
    (net (code "146") (name "unconnected-(IC6-CBUS2-Pad13)") (class "Default")
      (node (ref "IC6") (pin "13") (pinfunction "CBUS2_13") (pintype "bidirectional"))
    )
    (net (code "147") (name "unconnected-(IC6-CBUS3-Pad14)") (class "Default")
      (node (ref "IC6") (pin "14") (pinfunction "CBUS3_14") (pintype "bidirectional"))
    )
    (net (code "148") (name "unconnected-(IC6-CBUS4-Pad12)") (class "Default")
      (node (ref "IC6") (pin "12") (pinfunction "CBUS4_12") (pintype "bidirectional"))
    )
    (net (code "149") (name "unconnected-(IC6-OSCI-Pad27)") (class "Default")
      (node (ref "IC6") (pin "27") (pinfunction "OSCI_27") (pintype "input"))
    )
    (net (code "150") (name "unconnected-(IC6-OSCO-Pad28)") (class "Default")
      (node (ref "IC6") (pin "28") (pinfunction "OSCO_28") (pintype "output"))
    )
    (net (code "151") (name "unconnected-(IC6-~{CTS}-Pad11)") (class "Default")
      (node (ref "IC6") (pin "11") (pinfunction "~{CTS}_11") (pintype "input"))
    )
    (net (code "152") (name "unconnected-(IC6-~{DCD}-Pad10)") (class "Default")
      (node (ref "IC6") (pin "10") (pinfunction "~{DCD}_10") (pintype "input"))
    )
    (net (code "153") (name "unconnected-(IC6-~{DSR}-Pad9)") (class "Default")
      (node (ref "IC6") (pin "9") (pinfunction "~{DSR}_9") (pintype "input"))
    )
    (net (code "154") (name "unconnected-(IC6-~{DTR}-Pad2)") (class "Default")
      (node (ref "IC6") (pin "2") (pinfunction "~{DTR}_2") (pintype "output"))
    )
    (net (code "155") (name "unconnected-(IC6-~{RESET}-Pad19)") (class "Default")
      (node (ref "IC6") (pin "19") (pinfunction "~{RESET}_19") (pintype "input"))
    )
    (net (code "156") (name "unconnected-(IC6-~{RI}-Pad6)") (class "Default")
      (node (ref "IC6") (pin "6") (pinfunction "~{RI}_6") (pintype "input"))
    )
    (net (code "157") (name "unconnected-(IC6-~{RTS}-Pad3)") (class "Default")
      (node (ref "IC6") (pin "3") (pinfunction "~{RTS}_3") (pintype "output"))
    )
    (net (code "158") (name "unconnected-(IC7-OUT1-PadTAB)") (class "Default")
      (node (ref "IC7") (pin "TAB") (pinfunction "OUT1_TAB") (pintype "passive"))
    )
    (net (code "159") (name "unconnected-(SV1-Pad5)") (class "Default")
      (node (ref "SV1") (pin "5") (pinfunction "5_5") (pintype "passive"))
    )
    (net (code "160") (name "unconnected-(U$1-Pad1')") (class "Default")
      (node (ref "U$1") (pin "1'") (pinfunction "1'_1'") (pintype "output"))
    )
    (net (code "161") (name "unconnected-(U$1-Pad1)") (class "Default")
      (node (ref "U$1") (pin "1") (pinfunction "1_1") (pintype "output"))
    )
    (net (code "162") (name "unconnected-(U$1-Pad2')") (class "Default")
      (node (ref "U$1") (pin "2'") (pinfunction "2'_2'") (pintype "output"))
    )
    (net (code "163") (name "unconnected-(U$1-Pad3')") (class "Default")
      (node (ref "U$1") (pin "3'") (pinfunction "3'_3'") (pintype "output"))
    )
    (net (code "164") (name "unconnected-(U$1-Pad4')") (class "Default")
      (node (ref "U$1") (pin "4'") (pinfunction "4'_4'") (pintype "output"))
    )
    (net (code "165") (name "unconnected-(U$1-Pad5')") (class "Default")
      (node (ref "U$1") (pin "5'") (pinfunction "5'_5'") (pintype "output"))
    )
    (net (code "166") (name "unconnected-(U$1-Pad6')") (class "Default")
      (node (ref "U$1") (pin "6'") (pinfunction "6'_6'") (pintype "output"))
    )
    (net (code "167") (name "unconnected-(U$1-Pad7A)") (class "Default")
      (node (ref "U$1") (pin "7A") (pinfunction "7A_7A") (pintype "output"))
    )
    (net (code "168") (name "unconnected-(U$1-Pad8)") (class "Default")
      (node (ref "U$1") (pin "8") (pinfunction "8_8") (pintype "output"))
    )
    (net (code "169") (name "unconnected-(U$1-Pad8A)") (class "Default")
      (node (ref "U$1") (pin "8A") (pinfunction "8A_8A") (pintype "output"))
    )
    (net (code "170") (name "unconnected-(U$1-Pad9A)") (class "Default")
      (node (ref "U$1") (pin "9A") (pinfunction "9A_9A") (pintype "output"))
    )
    (net (code "171") (name "unconnected-(U$1-Pad10A)") (class "Default")
      (node (ref "U$1") (pin "10A") (pinfunction "10A_10A") (pintype "output"))
    )
    (net (code "172") (name "unconnected-(U$1-Pad11')") (class "Default")
      (node (ref "U$1") (pin "11'") (pinfunction "11'_11'") (pintype "output"))
    )
    (net (code "173") (name "unconnected-(U$1-Pad12')") (class "Default")
      (node (ref "U$1") (pin "12'") (pinfunction "12'_12'") (pintype "output"))
    )
    (net (code "174") (name "unconnected-(U$1-Pad13')") (class "Default")
      (node (ref "U$1") (pin "13'") (pinfunction "13'_13'") (pintype "output"))
    )
    (net (code "175") (name "unconnected-(U$1-Pad14')") (class "Default")
      (node (ref "U$1") (pin "14'") (pinfunction "14'_14'") (pintype "output"))
    )
    (net (code "176") (name "unconnected-(U$1-Pad15')") (class "Default")
      (node (ref "U$1") (pin "15'") (pinfunction "15'_15'") (pintype "output"))
    )
    (net (code "177") (name "unconnected-(U$1-Pad16')") (class "Default")
      (node (ref "U$1") (pin "16'") (pinfunction "16'_16'") (pintype "output"))
    )
    (net (code "178") (name "unconnected-(U$1-Pad17A)") (class "Default")
      (node (ref "U$1") (pin "17A") (pinfunction "17A_17A") (pintype "output"))
    )
    (net (code "179") (name "unconnected-(U$1-Pad17B)") (class "Default")
      (node (ref "U$1") (pin "17B") (pinfunction "17B_17B") (pintype "output"))
    )
    (net (code "180") (name "unconnected-(U$1-Pad18')") (class "Default")
      (node (ref "U$1") (pin "18'") (pinfunction "18'_18'") (pintype "output"))
    )
    (net (code "181") (name "unconnected-(U$1-Pad18)") (class "Default")
      (node (ref "U$1") (pin "18") (pinfunction "18_18") (pintype "output"))
    )
    (net (code "182") (name "unconnected-(U$1-Pad19')") (class "Default")
      (node (ref "U$1") (pin "19'") (pinfunction "19'_19'") (pintype "output"))
    )
    (net (code "183") (name "unconnected-(U$1-Pad19)") (class "Default")
      (node (ref "U$1") (pin "19") (pinfunction "19_19") (pintype "output"))
    )
    (net (code "184") (name "unconnected-(U$1-Pad20)") (class "Default")
      (node (ref "U$1") (pin "20") (pinfunction "20_20") (pintype "output"))
    )
    (net (code "185") (name "unconnected-(U$1-Pad20A)") (class "Default")
      (node (ref "U$1") (pin "20A") (pinfunction "20A_20A") (pintype "output"))
    )
    (net (code "186") (name "unconnected-(U$1-Pad21)") (class "Default")
      (node (ref "U$1") (pin "21") (pinfunction "21_21") (pintype "output"))
    )
    (net (code "187") (name "unconnected-(U$1-Pad21A)") (class "Default")
      (node (ref "U$1") (pin "21A") (pinfunction "21A_21A") (pintype "output"))
    )
    (net (code "188") (name "unconnected-(U$1-Pad22')") (class "Default")
      (node (ref "U$1") (pin "22'") (pinfunction "22'_22'") (pintype "output"))
    )
    (net (code "189") (name "unconnected-(U$1-Pad23')") (class "Default")
      (node (ref "U$1") (pin "23'") (pinfunction "23'_23'") (pintype "output"))
    )
    (net (code "190") (name "unconnected-(U$1-Pad24')") (class "Default")
      (node (ref "U$1") (pin "24'") (pinfunction "24'_24'") (pintype "output"))
    )
    (net (code "191") (name "unconnected-(U$1-Pad25')") (class "Default")
      (node (ref "U$1") (pin "25'") (pinfunction "25'_25'") (pintype "output"))
    )
    (net (code "192") (name "unconnected-(U$1-Pad26')") (class "Default")
      (node (ref "U$1") (pin "26'") (pinfunction "26'_26'") (pintype "output"))
    )
    (net (code "193") (name "unconnected-(U$1-Pad27')") (class "Default")
      (node (ref "U$1") (pin "27'") (pinfunction "27'_27'") (pintype "output"))
    )
    (net (code "194") (name "unconnected-(U$1-Pad28')") (class "Default")
      (node (ref "U$1") (pin "28'") (pinfunction "28'_28'") (pintype "output"))
    )
    (net (code "195") (name "unconnected-(U$1-Pad29')") (class "Default")
      (node (ref "U$1") (pin "29'") (pinfunction "29'_29'") (pintype "output"))
    )
    (net (code "196") (name "unconnected-(U$1-Pad30')") (class "Default")
      (node (ref "U$1") (pin "30'") (pinfunction "30'_30'") (pintype "output"))
    )
    (net (code "197") (name "unconnected-(U$1-Pad31')") (class "Default")
      (node (ref "U$1") (pin "31'") (pinfunction "31'_31'") (pintype "output"))
    )
    (net (code "198") (name "unconnected-(U$1-Pad32')") (class "Default")
      (node (ref "U$1") (pin "32'") (pinfunction "32'_32'") (pintype "output"))
    )
    (net (code "199") (name "unconnected-(U$1-Pad33')") (class "Default")
      (node (ref "U$1") (pin "33'") (pinfunction "33'_33'") (pintype "output"))
    )
    (net (code "200") (name "unconnected-(U$1-Pad34')") (class "Default")
      (node (ref "U$1") (pin "34'") (pinfunction "34'_34'") (pintype "output"))
    )
    (net (code "201") (name "unconnected-(U$1-Pad35)") (class "Default")
      (node (ref "U$1") (pin "35") (pinfunction "35_35") (pintype "output"))
    )
    (net (code "202") (name "unconnected-(U$1-Pad35A)") (class "Default")
      (node (ref "U$1") (pin "35A") (pinfunction "35A_35A") (pintype "output"))
    )
    (net (code "203") (name "unconnected-(U$1-Pad36')") (class "Default")
      (node (ref "U$1") (pin "36'") (pinfunction "36'_36'") (pintype "output"))
    )
    (net (code "204") (name "unconnected-(U$1-Pad37')") (class "Default")
      (node (ref "U$1") (pin "37'") (pinfunction "37'_37'") (pintype "output"))
    )
    (net (code "205") (name "unconnected-(U$1-Pad38')") (class "Default")
      (node (ref "U$1") (pin "38'") (pinfunction "38'_38'") (pintype "output"))
    )
    (net (code "206") (name "unconnected-(U$1-Pad39')") (class "Default")
      (node (ref "U$1") (pin "39'") (pinfunction "39'_39'") (pintype "output"))
    )
    (net (code "207") (name "unconnected-(U$1-Pad40')") (class "Default")
      (node (ref "U$1") (pin "40'") (pinfunction "40'_40'") (pintype "output"))
    )
    (net (code "208") (name "unconnected-(U$1-Pad41')") (class "Default")
      (node (ref "U$1") (pin "41'") (pinfunction "41'_41'") (pintype "output"))
    )
    (net (code "209") (name "unconnected-(U$1-Pad42')") (class "Default")
      (node (ref "U$1") (pin "42'") (pinfunction "42'_42'") (pintype "output"))
    )
    (net (code "210") (name "unconnected-(U$1-Pad43')") (class "Default")
      (node (ref "U$1") (pin "43'") (pinfunction "43'_43'") (pintype "output"))
    )
    (net (code "211") (name "unconnected-(U$1-Pad44')") (class "Default")
      (node (ref "U$1") (pin "44'") (pinfunction "44'_44'") (pintype "output"))
    )
    (net (code "212") (name "unconnected-(U$1-Pad45')") (class "Default")
      (node (ref "U$1") (pin "45'") (pinfunction "45'_45'") (pintype "output"))
    )
    (net (code "213") (name "unconnected-(U$1-Pad46')") (class "Default")
      (node (ref "U$1") (pin "46'") (pinfunction "46'_46'") (pintype "output"))
    )
    (net (code "214") (name "unconnected-(U$1-Pad47')") (class "Default")
      (node (ref "U$1") (pin "47'") (pinfunction "47'_47'") (pintype "output"))
    )
    (net (code "215") (name "unconnected-(U$1-Pad47)") (class "Default")
      (node (ref "U$1") (pin "47") (pinfunction "47_47") (pintype "output"))
    )
    (net (code "216") (name "unconnected-(U$1-Pad48')") (class "Default")
      (node (ref "U$1") (pin "48'") (pinfunction "48'_48'") (pintype "output"))
    )
    (net (code "217") (name "unconnected-(U$1-Pad48)") (class "Default")
      (node (ref "U$1") (pin "48") (pinfunction "48_48") (pintype "output"))
    )
    (net (code "218") (name "unconnected-(U$1-Pad49')") (class "Default")
      (node (ref "U$1") (pin "49'") (pinfunction "49'_49'") (pintype "output"))
    )
    (net (code "219") (name "unconnected-(U$1-Pad49)") (class "Default")
      (node (ref "U$1") (pin "49") (pinfunction "49_49") (pintype "output"))
    )
    (net (code "220") (name "unconnected-(U$1-Pad50')") (class "Default")
      (node (ref "U$1") (pin "50'") (pinfunction "50'_50'") (pintype "output"))
    )
    (net (code "221") (name "unconnected-(U$1-Pad51')") (class "Default")
      (node (ref "U$1") (pin "51'") (pinfunction "51'_51'") (pintype "output"))
    )
    (net (code "222") (name "unconnected-(U$1-Pad52')") (class "Default")
      (node (ref "U$1") (pin "52'") (pinfunction "52'_52'") (pintype "output"))
    )
    (net (code "223") (name "unconnected-(U$1-Pad53')") (class "Default")
      (node (ref "U$1") (pin "53'") (pinfunction "53'_53'") (pintype "output"))
    )
    (net (code "224") (name "unconnected-(U$1-Pad54')") (class "Default")
      (node (ref "U$1") (pin "54'") (pinfunction "54'_54'") (pintype "output"))
    )
    (net (code "225") (name "unconnected-(U$1-Pad55')") (class "Default")
      (node (ref "U$1") (pin "55'") (pinfunction "55'_55'") (pintype "output"))
    )
    (net (code "226") (name "unconnected-(U$1-Pad57)") (class "Default")
      (node (ref "U$1") (pin "57") (pinfunction "57_57") (pintype "output"))
    )
    (net (code "227") (name "unconnected-(U$1-Pad57A)") (class "Default")
      (node (ref "U$1") (pin "57A") (pinfunction "57A_57A") (pintype "output"))
    )
    (net (code "228") (name "unconnected-(U$1-Pad58)") (class "Default")
      (node (ref "U$1") (pin "58") (pinfunction "58_58") (pintype "output"))
    )
    (net (code "229") (name "unconnected-(U$1-Pad58A)") (class "Default")
      (node (ref "U$1") (pin "58A") (pinfunction "58A_58A") (pintype "output"))
    )
    (net (code "230") (name "unconnected-(U$1-Pad59)") (class "Default")
      (node (ref "U$1") (pin "59") (pinfunction "59_59") (pintype "output"))
    )
    (net (code "231") (name "unconnected-(U$1-Pad59A)") (class "Default")
      (node (ref "U$1") (pin "59A") (pinfunction "59A_59A") (pintype "output"))
    )
    (net (code "232") (name "unconnected-(U$1-Pad60)") (class "Default")
      (node (ref "U$1") (pin "60") (pinfunction "60_60") (pintype "output"))
    )
    (net (code "233") (name "unconnected-(U$1-Pad60A)") (class "Default")
      (node (ref "U$1") (pin "60A") (pinfunction "60A_60A") (pintype "output"))
    )
    (net (code "234") (name "unconnected-(U$1-Pad61')") (class "Default")
      (node (ref "U$1") (pin "61'") (pinfunction "61'_61'") (pintype "output"))
    )
    (net (code "235") (name "unconnected-(U$1-Pad61)") (class "Default")
      (node (ref "U$1") (pin "61") (pinfunction "61_61") (pintype "output"))
    )
    (net (code "236") (name "unconnected-(U$1-Pad62')") (class "Default")
      (node (ref "U$1") (pin "62'") (pinfunction "62'_62'") (pintype "output"))
    )
    (net (code "237") (name "unconnected-(U$1-Pad63')") (class "Default")
      (node (ref "U$1") (pin "63'") (pinfunction "63'_63'") (pintype "output"))
    )
    (net (code "238") (name "unconnected-(U$1-Pad64')") (class "Default")
      (node (ref "U$1") (pin "64'") (pinfunction "64'_64'") (pintype "output"))
    )
    (net (code "239") (name "unconnected-(U$1-Pad64)") (class "Default")
      (node (ref "U$1") (pin "64") (pinfunction "64_64") (pintype "output"))
    )
    (net (code "240") (name "unconnected-(U$1-Pad65')") (class "Default")
      (node (ref "U$1") (pin "65'") (pinfunction "65'_65'") (pintype "output"))
    )
    (net (code "241") (name "unconnected-(U$1-Pad65)") (class "Default")
      (node (ref "U$1") (pin "65") (pinfunction "65_65") (pintype "output"))
    )
    (net (code "242") (name "unconnected-(U$1-Pad66')") (class "Default")
      (node (ref "U$1") (pin "66'") (pinfunction "66'_66'") (pintype "output"))
    )
    (net (code "243") (name "unconnected-(U$1-Pad66)") (class "Default")
      (node (ref "U$1") (pin "66") (pinfunction "66_66") (pintype "output"))
    )
    (net (code "244") (name "unconnected-(U$1-Pad67')") (class "Default")
      (node (ref "U$1") (pin "67'") (pinfunction "67'_67'") (pintype "output"))
    )
    (net (code "245") (name "unconnected-(U$1-Pad67)") (class "Default")
      (node (ref "U$1") (pin "67") (pinfunction "67_67") (pintype "output"))
    )
    (net (code "246") (name "unconnected-(U$1-Pad68')") (class "Default")
      (node (ref "U$1") (pin "68'") (pinfunction "68'_68'") (pintype "output"))
    )
    (net (code "247") (name "unconnected-(U$1-Pad68)") (class "Default")
      (node (ref "U$1") (pin "68") (pinfunction "68_68") (pintype "output"))
    )
    (net (code "248") (name "unconnected-(U$1-Pad69')") (class "Default")
      (node (ref "U$1") (pin "69'") (pinfunction "69'_69'") (pintype "output"))
    )
    (net (code "249") (name "unconnected-(U$1-Pad70')") (class "Default")
      (node (ref "U$1") (pin "70'") (pinfunction "70'_70'") (pintype "output"))
    )
    (net (code "250") (name "unconnected-(U$1-Pad71')") (class "Default")
      (node (ref "U$1") (pin "71'") (pinfunction "71'_71'") (pintype "output"))
    )
    (net (code "251") (name "unconnected-(U$1-Pad72')") (class "Default")
      (node (ref "U$1") (pin "72'") (pinfunction "72'_72'") (pintype "output"))
    )
    (net (code "252") (name "unconnected-(U$1-Pad72)") (class "Default")
      (node (ref "U$1") (pin "72") (pinfunction "72_72") (pintype "output"))
    )
    (net (code "253") (name "unconnected-(U$1-Pad73')") (class "Default")
      (node (ref "U$1") (pin "73'") (pinfunction "73'_73'") (pintype "output"))
    )
    (net (code "254") (name "unconnected-(U$1-Pad74')") (class "Default")
      (node (ref "U$1") (pin "74'") (pinfunction "74'_74'") (pintype "output"))
    )
    (net (code "255") (name "unconnected-(U$2-3.3-2-Pad17)") (class "Default")
      (node (ref "U$2") (pin "17") (pinfunction "3.3-2_17") (pintype "bidirectional"))
    )
    (net (code "256") (name "unconnected-(U$2-5-2-Pad4)") (class "Default")
      (node (ref "U$2") (pin "4") (pinfunction "5-2_4") (pintype "bidirectional"))
    )
    (net (code "257") (name "unconnected-(U$2-12-Pad32)") (class "Default")
      (node (ref "U$2") (pin "32") (pinfunction "12_32") (pintype "bidirectional"))
    )
  )
)
